# mcu.net
KiCad netlist of a schematic drawn in Altium Designer
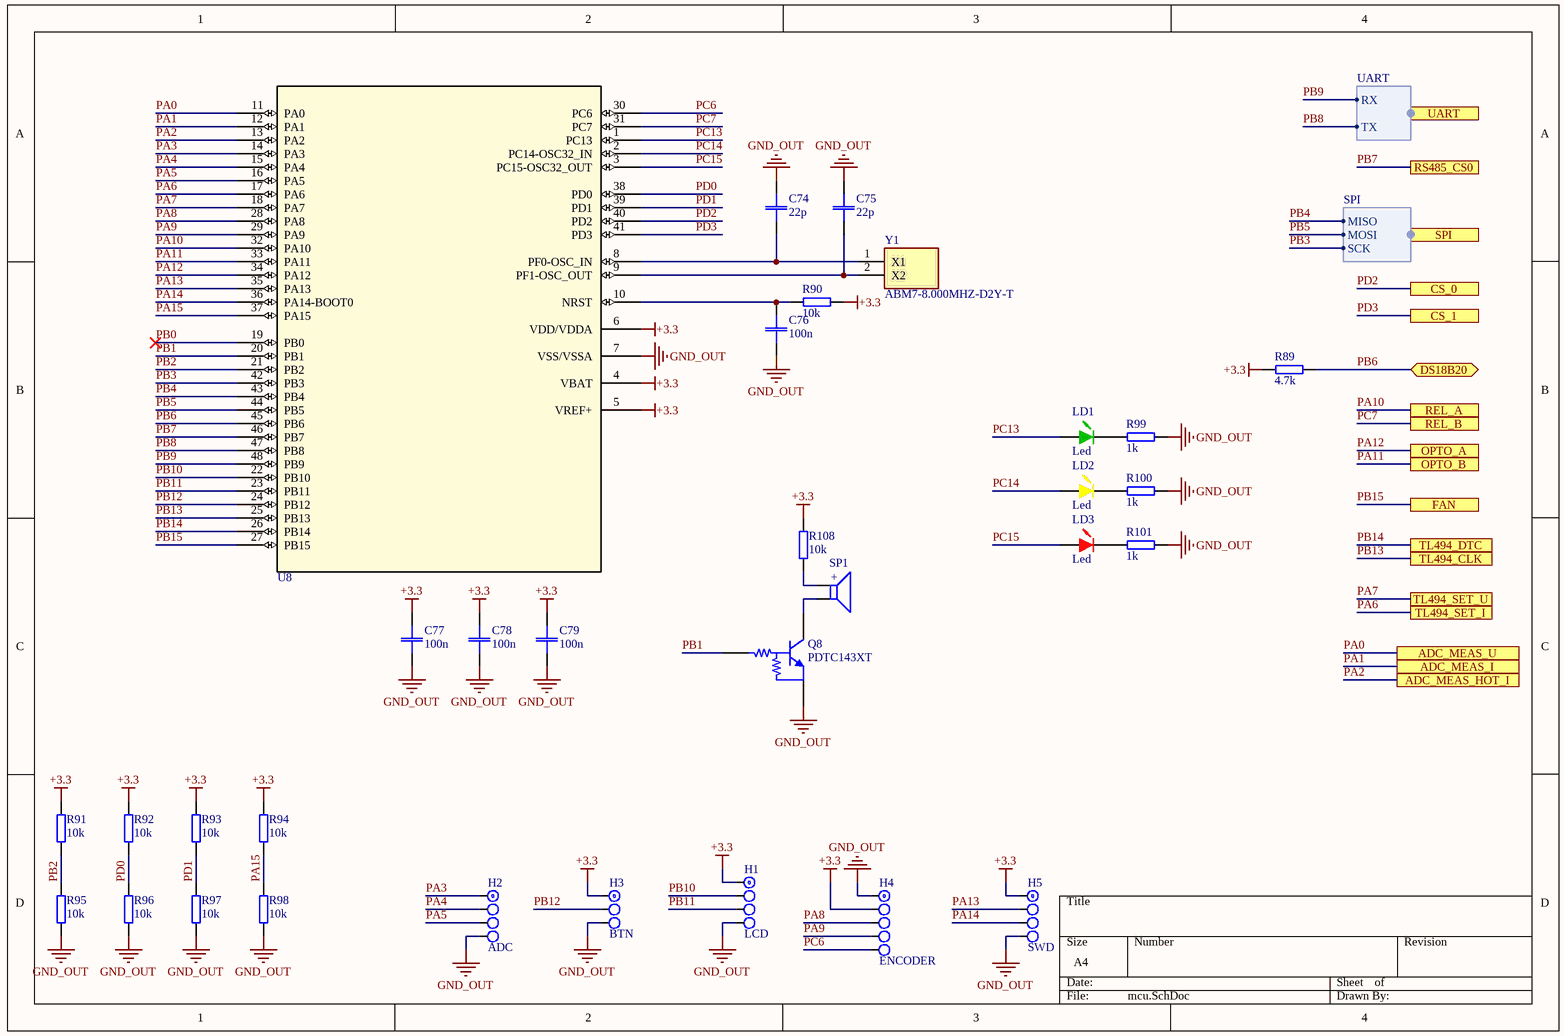
[diagram p0: mcu.SchDoc]

(export (version "E")
  (design (tool "Eeschema 10.0.6"))
  (components
    (comp (ref "C74") (value "22p") (footprint "CAP: 0603") (libsource (lib "PASSIVE") (part "C_SMD")))
    (comp (ref "C75") (value "22p") (footprint "CAP: 0603") (libsource (lib "PASSIVE") (part "C_SMD")))
    (comp (ref "C76") (value "100n") (footprint "CAP: 0603") (libsource (lib "PASSIVE") (part "C_SMD")))
    (comp (ref "C77") (value "100n") (footprint "CAP: 0603") (libsource (lib "PASSIVE") (part "C_SMD")))
    (comp (ref "C78") (value "100n") (footprint "CAP: 0603") (libsource (lib "PASSIVE") (part "C_SMD")))
    (comp (ref "C79") (value "100n") (footprint "CAP: 0603") (libsource (lib "PASSIVE") (part "C_SMD")))
    (comp (ref "H1") (value "LCD") (footprint "J1x4") (libsource (lib "Connektor") (part "H-1x4")))
    (comp (ref "H2") (value "ADC") (footprint "J1x4") (libsource (lib "Connektor") (part "H-1x4")))
    (comp (ref "H3") (value "BTN") (footprint "J1x3") (libsource (lib "Connektor") (part "H-1x3")))
    (comp (ref "H4") (value "ENCODER") (footprint "J1x5") (libsource (lib "Connektor") (part "H-1x5")))
    (comp (ref "H5") (value "SWD") (footprint "J1x4") (libsource (lib "Connektor") (part "H-1x4")))
    (comp (ref "LD1")
      (value "Led")
      (footprint "Led 0805-Green")
      (description "Green 565nm 15mcd")
      (libsource (lib "Ind LED-LCD") (part "Led 0805 KP-2012SGC"))
    )
    (comp (ref "LD2")
      (value "Led")
      (footprint "Led 0805-Yellow")
      (description "Yellow 590nm 8mcd")
      (libsource (lib "Ind LED-LCD") (part "Led 0805 KP-2012YC"))
    )
    (comp (ref "LD3")
      (value "Led")
      (footprint "Led 0805-Red")
      (description "Red  627nm 12mcd")
      (libsource (lib "Ind LED-LCD") (part "Led 0805 KP-2012EC"))
    )
    (comp (ref "Q8")
      (value "PDTC143XT")
      (footprint "SOT23_N")
      (description "NPN Resistor-equipped Transistor")
      (fields (field (name "PUBLISHER") "Altium Limited"))
      (libsource (lib "Philips Discrete BJT - Low Power") (part "PDTC143XT"))
    )
    (comp (ref "R89") (value "4.7k") (footprint "RES: 0603") (libsource (lib "PASSIVE") (part "R_SMD")))
    (comp (ref "R90") (value "10k") (footprint "RES: 0603") (libsource (lib "PASSIVE") (part "R_SMD")))
    (comp (ref "R91") (value "10k") (footprint "RES: 0603") (libsource (lib "PASSIVE") (part "R_SMD")))
    (comp (ref "R92") (value "10k") (footprint "RES: 0603") (libsource (lib "PASSIVE") (part "R_SMD")))
    (comp (ref "R93") (value "10k") (footprint "RES: 0603") (libsource (lib "PASSIVE") (part "R_SMD")))
    (comp (ref "R94") (value "10k") (footprint "RES: 0603") (libsource (lib "PASSIVE") (part "R_SMD")))
    (comp (ref "R95") (value "10k") (footprint "RES: 0603") (libsource (lib "PASSIVE") (part "R_SMD")))
    (comp (ref "R96") (value "10k") (footprint "RES: 0603") (libsource (lib "PASSIVE") (part "R_SMD")))
    (comp (ref "R97") (value "10k") (footprint "RES: 0603") (libsource (lib "PASSIVE") (part "R_SMD")))
    (comp (ref "R98") (value "10k") (footprint "RES: 0603") (libsource (lib "PASSIVE") (part "R_SMD")))
    (comp (ref "R99") (value "1k") (footprint "RES: 0603") (libsource (lib "PASSIVE") (part "R_SMD")))
    (comp (ref "R100") (value "1k") (footprint "RES: 0603") (libsource (lib "PASSIVE") (part "R_SMD")))
    (comp (ref "R101") (value "1k") (footprint "RES: 0603") (libsource (lib "PASSIVE") (part "R_SMD")))
    (comp (ref "R108") (value "10k") (footprint "RES: 0603") (libsource (lib "PASSIVE") (part "R_SMD")))
    (comp (ref "SP1") (value "~") (footprint "BUZ: D12mm  P7.6mm") (libsource (lib "OTHER") (part "BUZZER")))
    (comp (ref "U8")
      (value "STM32G070CBTx")
      (footprint "48-LQFP")
      (fields
        (field (name "MANUFACTURER_PART_NUMBER") "stm32g0_lqfp48_t2")
        (field (name "COPYRIGHT") "Copyright (C) 2018 Accelerated Designs. All rights reserved")
      )
      (libsource (lib "MCU") (part "STM32G070CBTx"))
    )
    (comp (ref "Y1")
      (value "ABM7-8.000MHZ-D2Y-T")
      (footprint "ABM78000MHZD2YT")
      (description "Crystal or Oscillator")
      (fields (field (name "MOUSER PART NUMBER") "815-ABM7-8-D2Y-T"))
      (libsource (lib "ExternalLib") (part "ABM7-8.000MHZ-D2Y-T"))
    )
  )
  (nets
    (net (code "3") (name "+3.3") (class "Default")
      (node (ref "C77") (pin "2") (pinfunction "2_2") (pintype "passive"))
      (node (ref "C78") (pin "2") (pinfunction "2_2") (pintype "passive"))
      (node (ref "C79") (pin "2") (pinfunction "2_2") (pintype "passive"))
      (node (ref "H1") (pin "1") (pinfunction "1_1") (pintype "passive"))
      (node (ref "H3") (pin "1") (pinfunction "1_1") (pintype "passive"))
      (node (ref "H4") (pin "2") (pinfunction "2_2") (pintype "passive"))
      (node (ref "H5") (pin "1") (pinfunction "1_1") (pintype "passive"))
      (node (ref "R108") (pin "1") (pinfunction "1_1") (pintype "passive"))
      (node (ref "R89") (pin "1") (pinfunction "1_1") (pintype "passive"))
      (node (ref "R90") (pin "2") (pinfunction "2_2") (pintype "passive"))
      (node (ref "R91") (pin "1") (pinfunction "1_1") (pintype "passive"))
      (node (ref "R92") (pin "1") (pinfunction "1_1") (pintype "passive"))
      (node (ref "R93") (pin "1") (pinfunction "1_1") (pintype "passive"))
      (node (ref "R94") (pin "1") (pinfunction "1_1") (pintype "passive"))
      (node (ref "U8") (pin "4") (pinfunction "VBAT_4") (pintype "power_in"))
      (node (ref "U8") (pin "5") (pinfunction "VREF+_5") (pintype "power_in"))
      (node (ref "U8") (pin "6") (pinfunction "VDD/VDDA_6") (pintype "power_in"))
    )
    (net (code "4") (name "/PA0") (class "Default")
      (node (ref "U8") (pin "11") (pinfunction "PA0_11") (pintype "bidirectional"))
    )
    (net (code "5") (name "/PA1") (class "Default")
      (node (ref "U8") (pin "12") (pinfunction "PA1_12") (pintype "bidirectional"))
    )
    (net (code "6") (name "/PA2") (class "Default")
      (node (ref "U8") (pin "13") (pinfunction "PA2_13") (pintype "bidirectional"))
    )
    (net (code "7") (name "/PA3") (class "Default")
      (node (ref "H2") (pin "1") (pinfunction "1_1") (pintype "passive"))
      (node (ref "U8") (pin "14") (pinfunction "PA3_14") (pintype "bidirectional"))
    )
    (net (code "8") (name "/PA4") (class "Default")
      (node (ref "H2") (pin "2") (pinfunction "2_2") (pintype "passive"))
      (node (ref "U8") (pin "15") (pinfunction "PA4_15") (pintype "bidirectional"))
    )
    (net (code "9") (name "/PA5") (class "Default")
      (node (ref "H2") (pin "3") (pinfunction "3_3") (pintype "passive"))
      (node (ref "U8") (pin "16") (pinfunction "PA5_16") (pintype "bidirectional"))
    )
    (net (code "10") (name "/PA6") (class "Default")
      (node (ref "U8") (pin "17") (pinfunction "PA6_17") (pintype "bidirectional"))
    )
    (net (code "11") (name "/PA7") (class "Default")
      (node (ref "U8") (pin "18") (pinfunction "PA7_18") (pintype "bidirectional"))
    )
    (net (code "12") (name "/PA8") (class "Default")
      (node (ref "H4") (pin "3") (pinfunction "3_3") (pintype "passive"))
      (node (ref "U8") (pin "28") (pinfunction "PA8_28") (pintype "bidirectional"))
    )
    (net (code "13") (name "/PA9") (class "Default")
      (node (ref "H4") (pin "4") (pinfunction "4_4") (pintype "passive"))
      (node (ref "U8") (pin "29") (pinfunction "PA9_29") (pintype "bidirectional"))
    )
    (net (code "14") (name "/PA10") (class "Default")
      (node (ref "U8") (pin "32") (pinfunction "PA10_32") (pintype "bidirectional"))
    )
    (net (code "15") (name "/PA11") (class "Default")
      (node (ref "U8") (pin "33") (pinfunction "PA11_33") (pintype "bidirectional"))
    )
    (net (code "16") (name "/PA12") (class "Default")
      (node (ref "U8") (pin "34") (pinfunction "PA12_34") (pintype "bidirectional"))
    )
    (net (code "17") (name "/PA13") (class "Default")
      (node (ref "H5") (pin "2") (pinfunction "2_2") (pintype "passive"))
      (node (ref "U8") (pin "35") (pinfunction "PA13_35") (pintype "bidirectional"))
    )
    (net (code "18") (name "/PA14") (class "Default")
      (node (ref "H5") (pin "3") (pinfunction "3_3") (pintype "passive"))
      (node (ref "U8") (pin "36") (pinfunction "PA14-BOOT0_36") (pintype "bidirectional"))
    )
    (net (code "19") (name "/PA15") (class "Default")
      (node (ref "R94") (pin "2") (pinfunction "2_2") (pintype "passive"))
      (node (ref "R98") (pin "1") (pinfunction "1_1") (pintype "passive"))
      (node (ref "U8") (pin "37") (pinfunction "PA15_37") (pintype "bidirectional"))
    )
    (net (code "20") (name "/PB0") (class "Default")
      (node (ref "U8") (pin "19") (pinfunction "PB0_19") (pintype "bidirectional+no_connect"))
    )
    (net (code "21") (name "/PB1") (class "Default")
      (node (ref "Q8") (pin "1") (pinfunction "B_1") (pintype "passive"))
      (node (ref "U8") (pin "20") (pinfunction "PB1_20") (pintype "bidirectional"))
    )
    (net (code "22") (name "/PB2") (class "Default")
      (node (ref "R91") (pin "2") (pinfunction "2_2") (pintype "passive"))
      (node (ref "R95") (pin "1") (pinfunction "1_1") (pintype "passive"))
      (node (ref "U8") (pin "21") (pinfunction "PB2_21") (pintype "bidirectional"))
    )
    (net (code "23") (name "/PB3") (class "Default")
      (node (ref "U8") (pin "42") (pinfunction "PB3_42") (pintype "bidirectional"))
    )
    (net (code "24") (name "/PB4") (class "Default")
      (node (ref "U8") (pin "43") (pinfunction "PB4_43") (pintype "bidirectional"))
    )
    (net (code "25") (name "/PB5") (class "Default")
      (node (ref "U8") (pin "44") (pinfunction "PB5_44") (pintype "bidirectional"))
    )
    (net (code "26") (name "/PB6") (class "Default")
      (node (ref "R89") (pin "2") (pinfunction "2_2") (pintype "passive"))
      (node (ref "U8") (pin "45") (pinfunction "PB6_45") (pintype "bidirectional"))
    )
    (net (code "27") (name "/PB7") (class "Default")
      (node (ref "U8") (pin "46") (pinfunction "PB7_46") (pintype "bidirectional"))
    )
    (net (code "28") (name "/PB8") (class "Default")
      (node (ref "U8") (pin "47") (pinfunction "PB8_47") (pintype "bidirectional"))
    )
    (net (code "29") (name "/PB9") (class "Default")
      (node (ref "U8") (pin "48") (pinfunction "PB9_48") (pintype "bidirectional"))
    )
    (net (code "30") (name "/PB10") (class "Default")
      (node (ref "H1") (pin "2") (pinfunction "2_2") (pintype "passive"))
      (node (ref "U8") (pin "22") (pinfunction "PB10_22") (pintype "bidirectional"))
    )
    (net (code "31") (name "/PB11") (class "Default")
      (node (ref "H1") (pin "3") (pinfunction "3_3") (pintype "passive"))
      (node (ref "U8") (pin "23") (pinfunction "PB11_23") (pintype "bidirectional"))
    )
    (net (code "32") (name "/PB12") (class "Default")
      (node (ref "H3") (pin "2") (pinfunction "2_2") (pintype "passive"))
      (node (ref "U8") (pin "24") (pinfunction "PB12_24") (pintype "bidirectional"))
    )
    (net (code "33") (name "/PB13") (class "Default")
      (node (ref "U8") (pin "25") (pinfunction "PB13_25") (pintype "bidirectional"))
    )
    (net (code "34") (name "/PB14") (class "Default")
      (node (ref "U8") (pin "26") (pinfunction "PB14_26") (pintype "bidirectional"))
    )
    (net (code "35") (name "/PB15") (class "Default")
      (node (ref "U8") (pin "27") (pinfunction "PB15_27") (pintype "bidirectional"))
    )
    (net (code "36") (name "/PC6") (class "Default")
      (node (ref "H4") (pin "5") (pinfunction "5_5") (pintype "passive"))
      (node (ref "U8") (pin "30") (pinfunction "PC6_30") (pintype "bidirectional"))
    )
    (net (code "37") (name "/PC7") (class "Default")
      (node (ref "U8") (pin "31") (pinfunction "PC7_31") (pintype "bidirectional"))
    )
    (net (code "38") (name "/PC13") (class "Default")
      (node (ref "LD1") (pin "1") (pinfunction "A_1") (pintype "passive"))
      (node (ref "U8") (pin "1") (pinfunction "PC13_1") (pintype "bidirectional"))
    )
    (net (code "39") (name "/PC14") (class "Default")
      (node (ref "LD2") (pin "1") (pinfunction "A_1") (pintype "passive"))
      (node (ref "U8") (pin "2") (pinfunction "PC14-OSC32_IN_2") (pintype "bidirectional"))
    )
    (net (code "40") (name "/PC15") (class "Default")
      (node (ref "LD3") (pin "1") (pinfunction "A_1") (pintype "passive"))
      (node (ref "U8") (pin "3") (pinfunction "PC15-OSC32_OUT_3") (pintype "bidirectional"))
    )
    (net (code "41") (name "/PD0") (class "Default")
      (node (ref "R92") (pin "2") (pinfunction "2_2") (pintype "passive"))
      (node (ref "R96") (pin "1") (pinfunction "1_1") (pintype "passive"))
      (node (ref "U8") (pin "38") (pinfunction "PD0_38") (pintype "bidirectional"))
    )
    (net (code "42") (name "/PD1") (class "Default")
      (node (ref "R93") (pin "2") (pinfunction "2_2") (pintype "passive"))
      (node (ref "R97") (pin "1") (pinfunction "1_1") (pintype "passive"))
      (node (ref "U8") (pin "39") (pinfunction "PD1_39") (pintype "bidirectional"))
    )
    (net (code "43") (name "/PD2") (class "Default")
      (node (ref "U8") (pin "40") (pinfunction "PD2_40") (pintype "bidirectional"))
    )
    (net (code "44") (name "/PD3") (class "Default")
      (node (ref "U8") (pin "41") (pinfunction "PD3_41") (pintype "bidirectional"))
    )
    (net (code "47") (name "GND_OUT") (class "Default")
      (node (ref "C74") (pin "2") (pinfunction "2_2") (pintype "passive"))
      (node (ref "C75") (pin "2") (pinfunction "2_2") (pintype "passive"))
      (node (ref "C76") (pin "1") (pinfunction "1_1") (pintype "passive"))
      (node (ref "C77") (pin "1") (pinfunction "1_1") (pintype "passive"))
      (node (ref "C78") (pin "1") (pinfunction "1_1") (pintype "passive"))
      (node (ref "C79") (pin "1") (pinfunction "1_1") (pintype "passive"))
      (node (ref "H1") (pin "4") (pinfunction "4_4") (pintype "passive"))
      (node (ref "H2") (pin "4") (pinfunction "4_4") (pintype "passive"))
      (node (ref "H3") (pin "3") (pinfunction "3_3") (pintype "passive"))
      (node (ref "H4") (pin "1") (pinfunction "1_1") (pintype "passive"))
      (node (ref "H5") (pin "4") (pinfunction "4_4") (pintype "passive"))
      (node (ref "Q8") (pin "2") (pinfunction "E_2") (pintype "passive"))
      (node (ref "R100") (pin "2") (pinfunction "2_2") (pintype "passive"))
      (node (ref "R101") (pin "2") (pinfunction "2_2") (pintype "passive"))
      (node (ref "R95") (pin "2") (pinfunction "2_2") (pintype "passive"))
      (node (ref "R96") (pin "2") (pinfunction "2_2") (pintype "passive"))
      (node (ref "R97") (pin "2") (pinfunction "2_2") (pintype "passive"))
      (node (ref "R98") (pin "2") (pinfunction "2_2") (pintype "passive"))
      (node (ref "R99") (pin "2") (pinfunction "2_2") (pintype "passive"))
      (node (ref "U8") (pin "7") (pinfunction "VSS/VSSA_7") (pintype "power_in"))
    )
    (net (code "48") (name "Net-(LD1-K)") (class "Default")
      (node (ref "LD1") (pin "2") (pinfunction "K_2") (pintype "passive"))
      (node (ref "R99") (pin "1") (pinfunction "1_1") (pintype "passive"))
    )
    (net (code "49") (name "Net-(LD2-K)") (class "Default")
      (node (ref "LD2") (pin "2") (pinfunction "K_2") (pintype "passive"))
      (node (ref "R100") (pin "1") (pinfunction "1_1") (pintype "passive"))
    )
    (net (code "50") (name "Net-(LD3-K)") (class "Default")
      (node (ref "LD3") (pin "2") (pinfunction "K_2") (pintype "passive"))
      (node (ref "R101") (pin "1") (pinfunction "1_1") (pintype "passive"))
    )
    (net (code "51") (name "Net-(Q8-C)") (class "Default")
      (node (ref "Q8") (pin "3") (pinfunction "C_3") (pintype "passive"))
      (node (ref "SP1") (pin "2") (pinfunction "2_2") (pintype "passive"))
    )
    (net (code "52") (name "Net-(R108-Pad2)") (class "Default")
      (node (ref "R108") (pin "2") (pinfunction "2_2") (pintype "passive"))
      (node (ref "SP1") (pin "1") (pinfunction "1_1") (pintype "passive"))
    )
    (net (code "53") (name "Net-(U8-NRST)") (class "Default")
      (node (ref "C76") (pin "2") (pinfunction "2_2") (pintype "passive"))
      (node (ref "R90") (pin "1") (pinfunction "1_1") (pintype "passive"))
      (node (ref "U8") (pin "10") (pinfunction "NRST_10") (pintype "bidirectional"))
    )
    (net (code "54") (name "Net-(U8-PF0-OSC_IN)") (class "Default")
      (node (ref "C74") (pin "1") (pinfunction "1_1") (pintype "passive"))
      (node (ref "U8") (pin "8") (pinfunction "PF0-OSC_IN_8") (pintype "bidirectional"))
      (node (ref "Y1") (pin "1") (pinfunction "X1_1") (pintype "passive"))
    )
    (net (code "55") (name "Net-(U8-PF1-OSC_OUT)") (class "Default")
      (node (ref "C75") (pin "1") (pinfunction "1_1") (pintype "passive"))
      (node (ref "U8") (pin "9") (pinfunction "PF1-OSC_OUT_9") (pintype "bidirectional"))
      (node (ref "Y1") (pin "2") (pinfunction "X2_2") (pintype "passive"))
    )
  )
)
